# 2.net
KiCad netlist of a schematic drawn in EAGLE
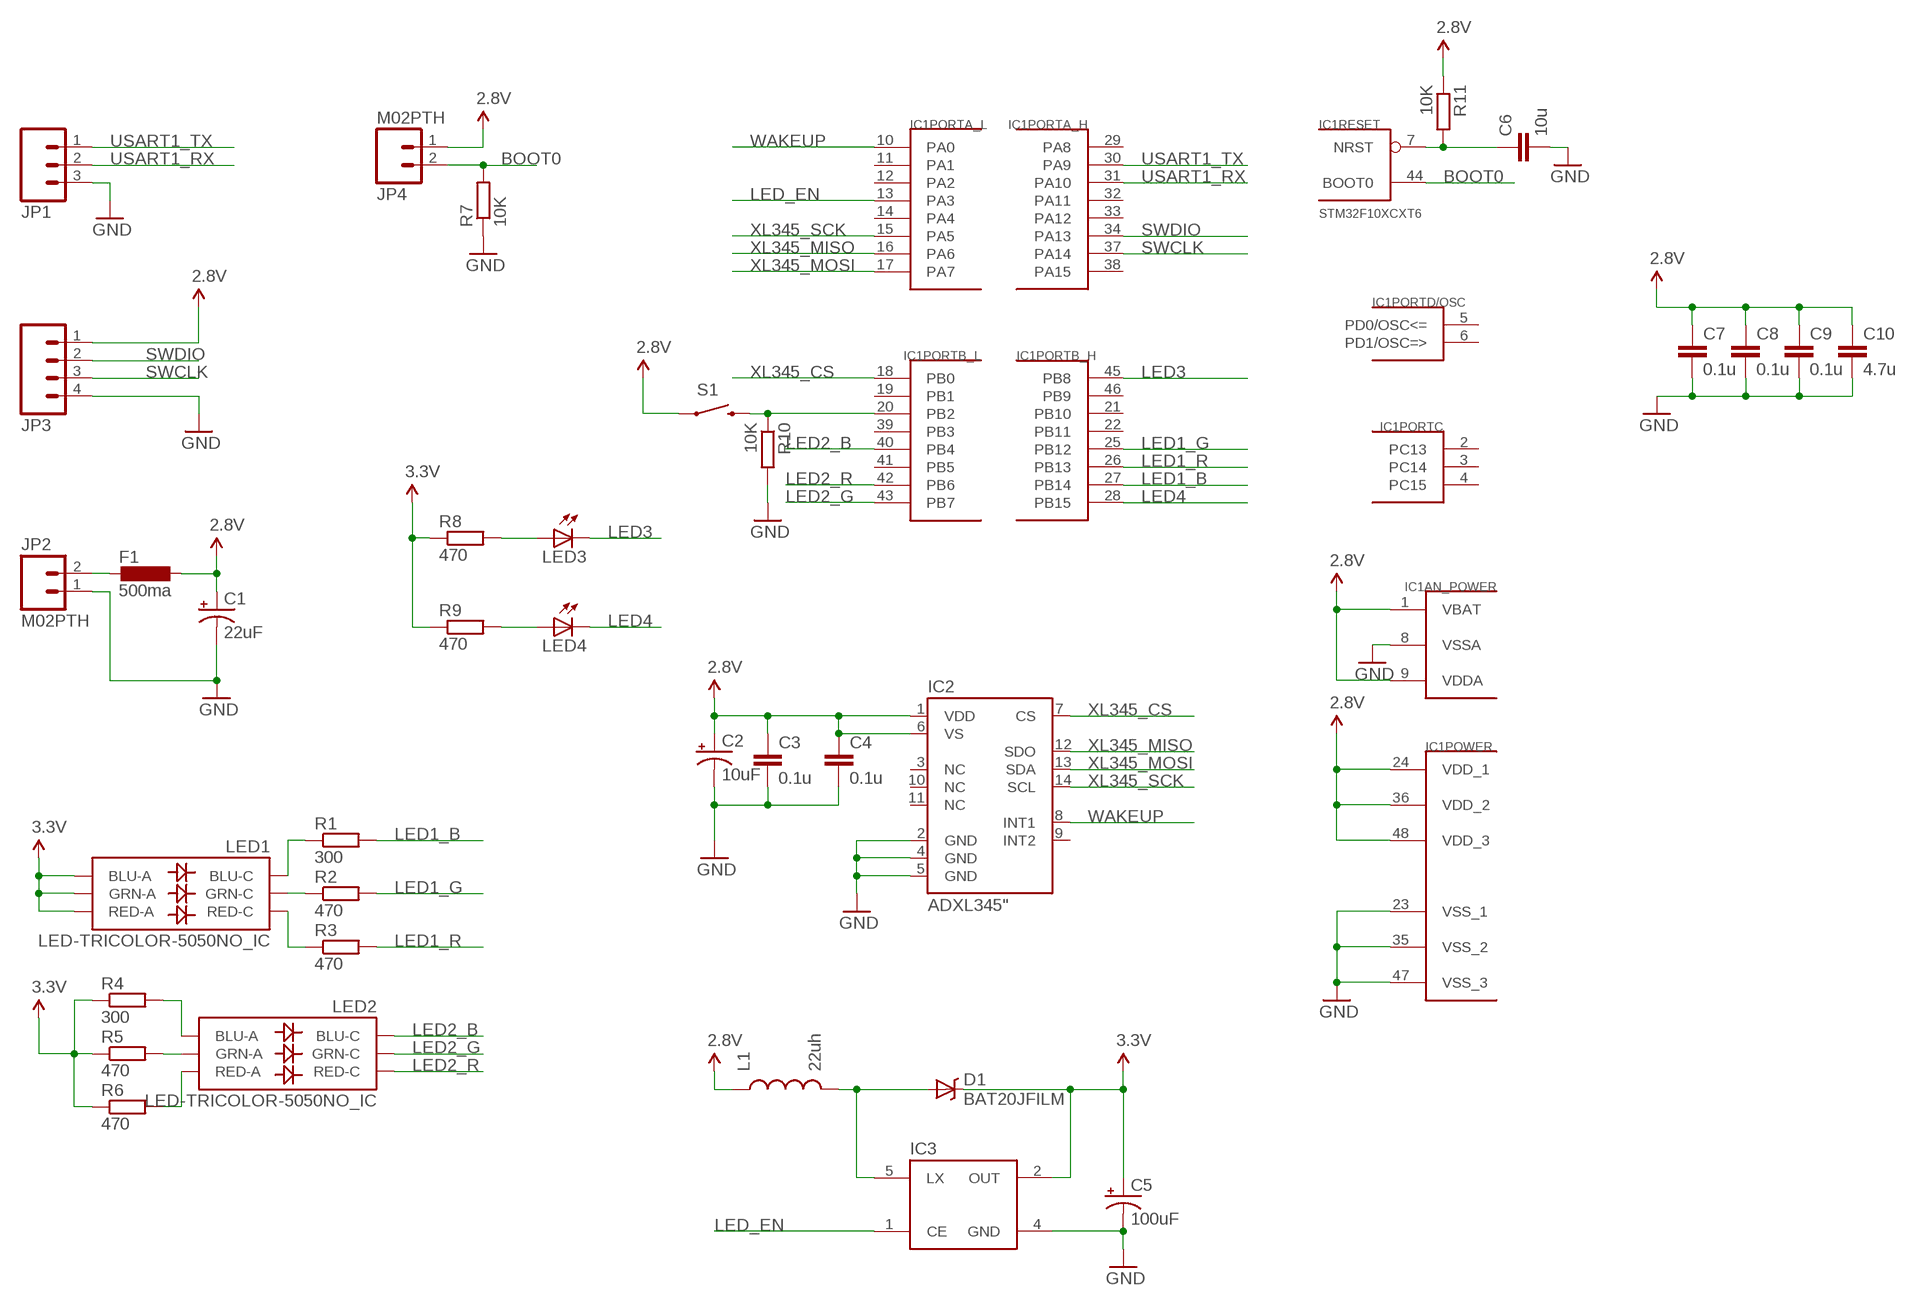
[diagram p0: schematic, sheet 1]

(export (version "E")
  (design (tool "Eeschema 10.0.6"))
  (components
    (comp (ref "C1")
      (value "22uF")
      (footprint "eagle-import:EIA3216")
      (libsource (lib "eagle-import") (part "10UF-16V-10%(TANT)"))
    )
    (comp (ref "C2")
      (value "10uF")
      (footprint "eagle-import:EIA3216")
      (libsource (lib "eagle-import") (part "10UF-16V-10%(TANT)"))
    )
    (comp (ref "C3")
      (value "0.1u")
      (footprint "eagle-import:C0603K")
      (libsource (lib "eagle-import") (part "C-EUC0603K"))
    )
    (comp (ref "C4")
      (value "0.1u")
      (footprint "eagle-import:C0603K")
      (libsource (lib "eagle-import") (part "C-EUC0603K"))
    )
    (comp (ref "C5")
      (value "100uF")
      (footprint "eagle-import:EIA3528")
      (libsource (lib "eagle-import") (part "47UF-TANT"))
    )
    (comp (ref "C6")
      (value "10u")
      (footprint "eagle-import:C0603K")
      (libsource (lib "eagle-import") (part "C-EUC0603K"))
    )
    (comp (ref "C7")
      (value "0.1u")
      (footprint "eagle-import:C0603K")
      (libsource (lib "eagle-import") (part "C-EUC0603K"))
    )
    (comp (ref "C8")
      (value "0.1u")
      (footprint "eagle-import:C0603K")
      (libsource (lib "eagle-import") (part "C-EUC0603K"))
    )
    (comp (ref "C9")
      (value "0.1u")
      (footprint "eagle-import:C0603K")
      (libsource (lib "eagle-import") (part "C-EUC0603K"))
    )
    (comp (ref "C10")
      (value "4.7u")
      (footprint "eagle-import:C0603K")
      (libsource (lib "eagle-import") (part "C-EUC0603K"))
    )
    (comp (ref "D1")
      (value "BAT20JFILM")
      (footprint "eagle-import:SOD-323")
      (libsource (lib "eagle-import") (part "BAT20JFILM"))
    )
    (comp (ref "F1")
      (value "500ma")
      (footprint "eagle-import:L2012C")
      (libsource (lib "eagle-import") (part "L-EUL2012C"))
    )
    (comp (ref "IC1")
      (value "STM32F10XCXT6")
      (footprint "eagle-import:TQFP48")
      (libsource (lib "eagle-import") (part "STM32F10XCXT6"))
    )
    (comp (ref "IC2")
      (value "ADXL345\"")
      (footprint "eagle-import:ADXL3451_1")
      (libsource (lib "eagle-import") (part "ADXL345{dblquote}"))
    )
    (comp (ref "IC3")
      (value "BL8530-XX2_RN")
      (footprint "eagle-import:SOT23-5")
      (libsource (lib "eagle-import") (part "BL8530-XX2_RN"))
    )
    (comp (ref "JP1")
      (value "M03PTH")
      (footprint "eagle-import:1X03")
      (libsource (lib "eagle-import") (part "M03PTH"))
    )
    (comp (ref "JP2")
      (value "M02PTH")
      (footprint "eagle-import:1X02")
      (libsource (lib "eagle-import") (part "M02PTH"))
    )
    (comp (ref "JP3")
      (value "M04PTH")
      (footprint "eagle-import:1X04")
      (libsource (lib "eagle-import") (part "M04PTH"))
    )
    (comp (ref "JP4")
      (value "M02PTH")
      (footprint "eagle-import:1X02")
      (libsource (lib "eagle-import") (part "M02PTH"))
    )
    (comp (ref "L1")
      (value "22uh")
      (footprint "eagle-import:VLF4012A")
      (libsource (lib "eagle-import") (part "INDUCTORVLF4012A"))
    )
    (comp (ref "LED1")
      (value "LED-TRICOLOR-5050NO_IC")
      (footprint "eagle-import:LED-TRICOLOR-5050")
      (libsource (lib "eagle-import") (part "LED-TRICOLOR-5050NO_IC"))
    )
    (comp (ref "LED2")
      (value "LED-TRICOLOR-5050NO_IC")
      (footprint "eagle-import:LED-TRICOLOR-5050")
      (libsource (lib "eagle-import") (part "LED-TRICOLOR-5050NO_IC"))
    )
    (comp (ref "LED3")
      (value "LED1206")
      (footprint "eagle-import:LED-1206")
      (libsource (lib "eagle-import") (part "LED1206"))
    )
    (comp (ref "LED4")
      (value "LED1206")
      (footprint "eagle-import:LED-1206")
      (libsource (lib "eagle-import") (part "LED1206"))
    )
    (comp (ref "R1")
      (value "300")
      (footprint "eagle-import:R0603")
      (libsource (lib "eagle-import") (part "R-EU_R0603"))
    )
    (comp (ref "R2")
      (value "470")
      (footprint "eagle-import:R0603")
      (libsource (lib "eagle-import") (part "R-EU_R0603"))
    )
    (comp (ref "R3")
      (value "470")
      (footprint "eagle-import:R0603")
      (libsource (lib "eagle-import") (part "R-EU_R0603"))
    )
    (comp (ref "R4")
      (value "300")
      (footprint "eagle-import:R0603")
      (libsource (lib "eagle-import") (part "R-EU_R0603"))
    )
    (comp (ref "R5")
      (value "470")
      (footprint "eagle-import:R0603")
      (libsource (lib "eagle-import") (part "R-EU_R0603"))
    )
    (comp (ref "R6")
      (value "470")
      (footprint "eagle-import:R0603")
      (libsource (lib "eagle-import") (part "R-EU_R0603"))
    )
    (comp (ref "R7")
      (value "10K")
      (footprint "eagle-import:R0603")
      (libsource (lib "eagle-import") (part "R-EU_R0603"))
    )
    (comp (ref "R8")
      (value "470")
      (footprint "eagle-import:R0603")
      (libsource (lib "eagle-import") (part "R-EU_R0603"))
    )
    (comp (ref "R9")
      (value "470")
      (footprint "eagle-import:R0603")
      (libsource (lib "eagle-import") (part "R-EU_R0603"))
    )
    (comp (ref "R10")
      (value "10K")
      (footprint "eagle-import:R0603")
      (libsource (lib "eagle-import") (part "R-EU_R0603"))
    )
    (comp (ref "R11")
      (value "10K")
      (footprint "eagle-import:R0603")
      (libsource (lib "eagle-import") (part "R-EU_R0603"))
    )
    (comp (ref "S1")
      (value "SWITCH-MOMENTARY-2-SMD-1101NE")
      (footprint "eagle-import:TACTILE-SWITCH-1101NE")
      (libsource (lib "eagle-import") (part "SWITCH-MOMENTARY-2-SMD-1101NE"))
    )
  )
  (nets
    (net (code "1") (name "/BOOT0") (class "Default")
      (node (ref "IC1") (pin "44") (pinfunction "BOOT0_44") (pintype "input"))
      (node (ref "JP4") (pin "2") (pinfunction "2_2") (pintype "passive"))
      (node (ref "R7") (pin "2") (pinfunction "2_2") (pintype "passive"))
    )
    (net (code "2") (name "/LED1_B") (class "Default")
      (node (ref "IC1") (pin "27") (pinfunction "PB14_27") (pintype "bidirectional"))
      (node (ref "R1") (pin "2") (pinfunction "2_2") (pintype "passive"))
    )
    (net (code "3") (name "/LED1_G") (class "Default")
      (node (ref "IC1") (pin "25") (pinfunction "PB12_25") (pintype "bidirectional"))
      (node (ref "R2") (pin "2") (pinfunction "2_2") (pintype "passive"))
    )
    (net (code "4") (name "/LED1_R") (class "Default")
      (node (ref "IC1") (pin "26") (pinfunction "PB13_26") (pintype "bidirectional"))
      (node (ref "R3") (pin "2") (pinfunction "2_2") (pintype "passive"))
    )
    (net (code "5") (name "/LED2_B") (class "Default")
      (node (ref "IC1") (pin "40") (pinfunction "PB4_40") (pintype "bidirectional"))
      (node (ref "LED2") (pin "4") (pinfunction "BLU-C_4") (pintype "bidirectional"))
    )
    (net (code "6") (name "/LED2_G") (class "Default")
      (node (ref "IC1") (pin "43") (pinfunction "PB7_43") (pintype "bidirectional"))
      (node (ref "LED2") (pin "6") (pinfunction "GRN-C_6") (pintype "bidirectional"))
    )
    (net (code "7") (name "/LED2_R") (class "Default")
      (node (ref "IC1") (pin "42") (pinfunction "PB6_42") (pintype "bidirectional"))
      (node (ref "LED2") (pin "5") (pinfunction "RED-C_5") (pintype "bidirectional"))
    )
    (net (code "8") (name "/LED3") (class "Default")
      (node (ref "IC1") (pin "45") (pinfunction "PB8_45") (pintype "bidirectional"))
      (node (ref "LED3") (pin "C") (pinfunction "C_C") (pintype "passive"))
    )
    (net (code "9") (name "/LED4") (class "Default")
      (node (ref "IC1") (pin "28") (pinfunction "PB15_28") (pintype "bidirectional"))
      (node (ref "LED4") (pin "C") (pinfunction "C_C") (pintype "passive"))
    )
    (net (code "10") (name "/LED_EN") (class "Default")
      (node (ref "IC1") (pin "13") (pinfunction "PA3_13") (pintype "bidirectional"))
      (node (ref "IC3") (pin "1") (pinfunction "CE_1") (pintype "bidirectional"))
    )
    (net (code "11") (name "/SWCLK") (class "Default")
      (node (ref "IC1") (pin "37") (pinfunction "PA14_37") (pintype "bidirectional"))
      (node (ref "JP3") (pin "3") (pinfunction "3_3") (pintype "passive"))
    )
    (net (code "12") (name "/SWDIO") (class "Default")
      (node (ref "IC1") (pin "34") (pinfunction "PA13_34") (pintype "bidirectional"))
      (node (ref "JP3") (pin "2") (pinfunction "2_2") (pintype "passive"))
    )
    (net (code "13") (name "/USART1_RX") (class "Default")
      (node (ref "IC1") (pin "31") (pinfunction "PA10_31") (pintype "bidirectional"))
      (node (ref "JP1") (pin "2") (pinfunction "2_2") (pintype "passive"))
    )
    (net (code "14") (name "/USART1_TX") (class "Default")
      (node (ref "IC1") (pin "30") (pinfunction "PA9_30") (pintype "bidirectional"))
      (node (ref "JP1") (pin "1") (pinfunction "1_1") (pintype "passive"))
    )
    (net (code "15") (name "/WAKEUP") (class "Default")
      (node (ref "IC1") (pin "10") (pinfunction "PA0_10") (pintype "bidirectional"))
      (node (ref "IC2") (pin "8") (pinfunction "INT1_8") (pintype "bidirectional"))
    )
    (net (code "16") (name "/XL345_CS") (class "Default")
      (node (ref "IC1") (pin "18") (pinfunction "PB0_18") (pintype "bidirectional"))
      (node (ref "IC2") (pin "7") (pinfunction "CS_7") (pintype "bidirectional"))
    )
    (net (code "17") (name "/XL345_MISO") (class "Default")
      (node (ref "IC1") (pin "16") (pinfunction "PA6_16") (pintype "bidirectional"))
      (node (ref "IC2") (pin "12") (pinfunction "SDO_12") (pintype "bidirectional"))
    )
    (net (code "18") (name "/XL345_MOSI") (class "Default")
      (node (ref "IC1") (pin "17") (pinfunction "PA7_17") (pintype "bidirectional"))
      (node (ref "IC2") (pin "13") (pinfunction "SDA_13") (pintype "bidirectional"))
    )
    (net (code "19") (name "/XL345_SCK") (class "Default")
      (node (ref "IC1") (pin "15") (pinfunction "PA5_15") (pintype "bidirectional"))
      (node (ref "IC2") (pin "14") (pinfunction "SCL_14") (pintype "bidirectional"))
    )
    (net (code "20") (name "2.8V") (class "Default")
      (node (ref "C1") (pin "A") (pinfunction "+_A") (pintype "passive"))
      (node (ref "C10") (pin "1") (pinfunction "1_1") (pintype "passive"))
      (node (ref "C2") (pin "A") (pinfunction "+_A") (pintype "passive"))
      (node (ref "C3") (pin "1") (pinfunction "1_1") (pintype "passive"))
      (node (ref "C4") (pin "1") (pinfunction "1_1") (pintype "passive"))
      (node (ref "C7") (pin "1") (pinfunction "1_1") (pintype "passive"))
      (node (ref "C8") (pin "1") (pinfunction "1_1") (pintype "passive"))
      (node (ref "C9") (pin "1") (pinfunction "1_1") (pintype "passive"))
      (node (ref "F1") (pin "1") (pinfunction "1_1") (pintype "passive"))
      (node (ref "IC1") (pin "1") (pinfunction "VBAT_1") (pintype "power_in"))
      (node (ref "IC1") (pin "24") (pinfunction "VDD_1_24") (pintype "power_in"))
      (node (ref "IC1") (pin "36") (pinfunction "VDD_2_36") (pintype "power_in"))
      (node (ref "IC1") (pin "48") (pinfunction "VDD_3_48") (pintype "power_in"))
      (node (ref "IC1") (pin "9") (pinfunction "VDDA_9") (pintype "power_in"))
      (node (ref "IC2") (pin "1") (pinfunction "VDD_1") (pintype "bidirectional"))
      (node (ref "IC2") (pin "6") (pinfunction "VS_6") (pintype "bidirectional"))
      (node (ref "JP3") (pin "1") (pinfunction "1_1") (pintype "passive"))
      (node (ref "JP4") (pin "1") (pinfunction "1_1") (pintype "passive"))
      (node (ref "L1") (pin "P$1") (pinfunction "1_P$1") (pintype "passive"))
      (node (ref "R11") (pin "1") (pinfunction "1_1") (pintype "passive"))
      (node (ref "S1") (pin "P$1") (pinfunction "1_P$1") (pintype "passive"))
    )
    (net (code "21") (name "3.3V") (class "Default")
      (node (ref "C5") (pin "A") (pinfunction "+_A") (pintype "passive"))
      (node (ref "D1") (pin "1") (pinfunction "C_1") (pintype "passive"))
      (node (ref "IC3") (pin "2") (pinfunction "OUT_2") (pintype "bidirectional"))
      (node (ref "LED1") (pin "1") (pinfunction "GRN-A_1") (pintype "bidirectional"))
      (node (ref "LED1") (pin "2") (pinfunction "RED-A_2") (pintype "bidirectional"))
      (node (ref "LED1") (pin "3") (pinfunction "BLU-A_3") (pintype "bidirectional"))
      (node (ref "R4") (pin "1") (pinfunction "1_1") (pintype "passive"))
      (node (ref "R5") (pin "1") (pinfunction "1_1") (pintype "passive"))
      (node (ref "R6") (pin "1") (pinfunction "1_1") (pintype "passive"))
      (node (ref "R8") (pin "1") (pinfunction "1_1") (pintype "passive"))
      (node (ref "R9") (pin "1") (pinfunction "1_1") (pintype "passive"))
    )
    (net (code "22") (name "GND") (class "Default")
      (node (ref "C1") (pin "C") (pinfunction "-_C") (pintype "passive"))
      (node (ref "C10") (pin "2") (pinfunction "2_2") (pintype "passive"))
      (node (ref "C2") (pin "C") (pinfunction "-_C") (pintype "passive"))
      (node (ref "C3") (pin "2") (pinfunction "2_2") (pintype "passive"))
      (node (ref "C4") (pin "2") (pinfunction "2_2") (pintype "passive"))
      (node (ref "C5") (pin "C") (pinfunction "-_C") (pintype "passive"))
      (node (ref "C6") (pin "2") (pinfunction "2_2") (pintype "passive"))
      (node (ref "C7") (pin "2") (pinfunction "2_2") (pintype "passive"))
      (node (ref "C8") (pin "2") (pinfunction "2_2") (pintype "passive"))
      (node (ref "C9") (pin "2") (pinfunction "2_2") (pintype "passive"))
      (node (ref "IC1") (pin "23") (pinfunction "VSS_1_23") (pintype "power_in"))
      (node (ref "IC1") (pin "35") (pinfunction "VSS_2_35") (pintype "power_in"))
      (node (ref "IC1") (pin "47") (pinfunction "VSS_3_47") (pintype "power_in"))
      (node (ref "IC1") (pin "8") (pinfunction "VSSA_8") (pintype "power_in"))
      (node (ref "IC2") (pin "2") (pinfunction "GND_2") (pintype "bidirectional"))
      (node (ref "IC2") (pin "4") (pinfunction "GND_4") (pintype "bidirectional"))
      (node (ref "IC2") (pin "5") (pinfunction "GND_5") (pintype "bidirectional"))
      (node (ref "IC3") (pin "4") (pinfunction "GND_4") (pintype "bidirectional"))
      (node (ref "JP1") (pin "3") (pinfunction "3_3") (pintype "passive"))
      (node (ref "JP2") (pin "1") (pinfunction "1_1") (pintype "passive"))
      (node (ref "JP3") (pin "4") (pinfunction "4_4") (pintype "passive"))
      (node (ref "R10") (pin "2") (pinfunction "2_2") (pintype "passive"))
      (node (ref "R7") (pin "1") (pinfunction "1_1") (pintype "passive"))
    )
    (net (code "23") (name "Net-(D1-A)") (class "Default")
      (node (ref "D1") (pin "2") (pinfunction "A_2") (pintype "passive"))
      (node (ref "IC3") (pin "5") (pinfunction "LX_5") (pintype "bidirectional"))
      (node (ref "L1") (pin "P$2") (pinfunction "2_P$2") (pintype "passive"))
    )
    (net (code "24") (name "Net-(F1-Pad2)") (class "Default")
      (node (ref "F1") (pin "2") (pinfunction "2_2") (pintype "passive"))
      (node (ref "JP2") (pin "2") (pinfunction "2_2") (pintype "passive"))
    )
    (net (code "25") (name "Net-(IC1E-PB2)") (class "Default")
      (node (ref "IC1") (pin "20") (pinfunction "PB2_20") (pintype "bidirectional"))
      (node (ref "R10") (pin "1") (pinfunction "1_1") (pintype "passive"))
      (node (ref "S1") (pin "P$2") (pinfunction "2_P$2") (pintype "passive"))
    )
    (net (code "26") (name "Net-(IC1I-NRST)") (class "Default")
      (node (ref "C6") (pin "1") (pinfunction "1_1") (pintype "passive"))
      (node (ref "IC1") (pin "7") (pinfunction "NRST_7") (pintype "input"))
      (node (ref "R11") (pin "2") (pinfunction "2_2") (pintype "passive"))
    )
    (net (code "27") (name "Net-(LED1-BLU-C)") (class "Default")
      (node (ref "LED1") (pin "4") (pinfunction "BLU-C_4") (pintype "bidirectional"))
      (node (ref "R1") (pin "1") (pinfunction "1_1") (pintype "passive"))
    )
    (net (code "28") (name "Net-(LED1-GRN-C)") (class "Default")
      (node (ref "LED1") (pin "6") (pinfunction "GRN-C_6") (pintype "bidirectional"))
      (node (ref "R2") (pin "1") (pinfunction "1_1") (pintype "passive"))
    )
    (net (code "29") (name "Net-(LED1-RED-C)") (class "Default")
      (node (ref "LED1") (pin "5") (pinfunction "RED-C_5") (pintype "bidirectional"))
      (node (ref "R3") (pin "1") (pinfunction "1_1") (pintype "passive"))
    )
    (net (code "30") (name "Net-(LED2-BLU-A)") (class "Default")
      (node (ref "LED2") (pin "3") (pinfunction "BLU-A_3") (pintype "bidirectional"))
      (node (ref "R4") (pin "2") (pinfunction "2_2") (pintype "passive"))
    )
    (net (code "31") (name "Net-(LED2-GRN-A)") (class "Default")
      (node (ref "LED2") (pin "1") (pinfunction "GRN-A_1") (pintype "bidirectional"))
      (node (ref "R5") (pin "2") (pinfunction "2_2") (pintype "passive"))
    )
    (net (code "32") (name "Net-(LED2-RED-A)") (class "Default")
      (node (ref "LED2") (pin "2") (pinfunction "RED-A_2") (pintype "bidirectional"))
      (node (ref "R6") (pin "2") (pinfunction "2_2") (pintype "passive"))
    )
    (net (code "33") (name "Net-(LED3-PadA)") (class "Default")
      (node (ref "LED3") (pin "A") (pinfunction "A_A") (pintype "passive"))
      (node (ref "R8") (pin "2") (pinfunction "2_2") (pintype "passive"))
    )
    (net (code "34") (name "Net-(LED4-PadA)") (class "Default")
      (node (ref "LED4") (pin "A") (pinfunction "A_A") (pintype "passive"))
      (node (ref "R9") (pin "2") (pinfunction "2_2") (pintype "passive"))
    )
    (net (code "35") (name "unconnected-(IC1B-PA8-Pad29)") (class "Default")
      (node (ref "IC1") (pin "29") (pinfunction "PA8_29") (pintype "bidirectional"))
    )
    (net (code "36") (name "unconnected-(IC1B-PA11-Pad32)") (class "Default")
      (node (ref "IC1") (pin "32") (pinfunction "PA11_32") (pintype "bidirectional"))
    )
    (net (code "37") (name "unconnected-(IC1B-PA12-Pad33)") (class "Default")
      (node (ref "IC1") (pin "33") (pinfunction "PA12_33") (pintype "bidirectional"))
    )
    (net (code "38") (name "unconnected-(IC1B-PA15-Pad38)") (class "Default")
      (node (ref "IC1") (pin "38") (pinfunction "PA15_38") (pintype "bidirectional"))
    )
    (net (code "39") (name "unconnected-(IC1C-PA1-Pad11)") (class "Default")
      (node (ref "IC1") (pin "11") (pinfunction "PA1_11") (pintype "bidirectional"))
    )
    (net (code "40") (name "unconnected-(IC1C-PA2-Pad12)") (class "Default")
      (node (ref "IC1") (pin "12") (pinfunction "PA2_12") (pintype "bidirectional"))
    )
    (net (code "41") (name "unconnected-(IC1C-PA4-Pad14)") (class "Default")
      (node (ref "IC1") (pin "14") (pinfunction "PA4_14") (pintype "bidirectional"))
    )
    (net (code "42") (name "unconnected-(IC1D-PB9-Pad46)") (class "Default")
      (node (ref "IC1") (pin "46") (pinfunction "PB9_46") (pintype "bidirectional"))
    )
    (net (code "43") (name "unconnected-(IC1D-PB10-Pad21)") (class "Default")
      (node (ref "IC1") (pin "21") (pinfunction "PB10_21") (pintype "bidirectional"))
    )
    (net (code "44") (name "unconnected-(IC1D-PB11-Pad22)") (class "Default")
      (node (ref "IC1") (pin "22") (pinfunction "PB11_22") (pintype "bidirectional"))
    )
    (net (code "45") (name "unconnected-(IC1E-PB1-Pad19)") (class "Default")
      (node (ref "IC1") (pin "19") (pinfunction "PB1_19") (pintype "bidirectional"))
    )
    (net (code "46") (name "unconnected-(IC1E-PB3-Pad39)") (class "Default")
      (node (ref "IC1") (pin "39") (pinfunction "PB3_39") (pintype "bidirectional"))
    )
    (net (code "47") (name "unconnected-(IC1E-PB5-Pad41)") (class "Default")
      (node (ref "IC1") (pin "41") (pinfunction "PB5_41") (pintype "bidirectional"))
    )
    (net (code "48") (name "unconnected-(IC1F-PC13-Pad2)") (class "Default")
      (node (ref "IC1") (pin "2") (pinfunction "PC13_2") (pintype "bidirectional"))
    )
    (net (code "49") (name "unconnected-(IC1F-PC14-Pad3)") (class "Default")
      (node (ref "IC1") (pin "3") (pinfunction "PC14_3") (pintype "bidirectional"))
    )
    (net (code "50") (name "unconnected-(IC1F-PC15-Pad4)") (class "Default")
      (node (ref "IC1") (pin "4") (pinfunction "PC15_4") (pintype "bidirectional"))
    )
    (net (code "51") (name "unconnected-(IC1G-PD0{slash}OSC<=-Pad5)") (class "Default")
      (node (ref "IC1") (pin "5") (pinfunction "PD0/OSC<=_5") (pintype "bidirectional"))
    )
    (net (code "52") (name "unconnected-(IC1G-PD1{slash}OSC=>-Pad6)") (class "Default")
      (node (ref "IC1") (pin "6") (pinfunction "PD1/OSC=>_6") (pintype "bidirectional"))
    )
    (net (code "53") (name "unconnected-(IC2-INT2-Pad9)") (class "Default")
      (node (ref "IC2") (pin "9") (pinfunction "INT2_9") (pintype "bidirectional"))
    )
    (net (code "54") (name "unconnected-(IC2-NC-Pad3)") (class "Default")
      (node (ref "IC2") (pin "3") (pinfunction "NC_3") (pintype "bidirectional"))
    )
    (net (code "55") (name "unconnected-(IC2-NC-Pad10)") (class "Default")
      (node (ref "IC2") (pin "10") (pinfunction "NC_10") (pintype "bidirectional"))
    )
    (net (code "56") (name "unconnected-(IC2-NC-Pad11)") (class "Default")
      (node (ref "IC2") (pin "11") (pinfunction "NC_11") (pintype "bidirectional"))
    )
  )
)
